# Sony_PSP_USB-C.net
KiCad netlist of a schematic drawn in EAGLE
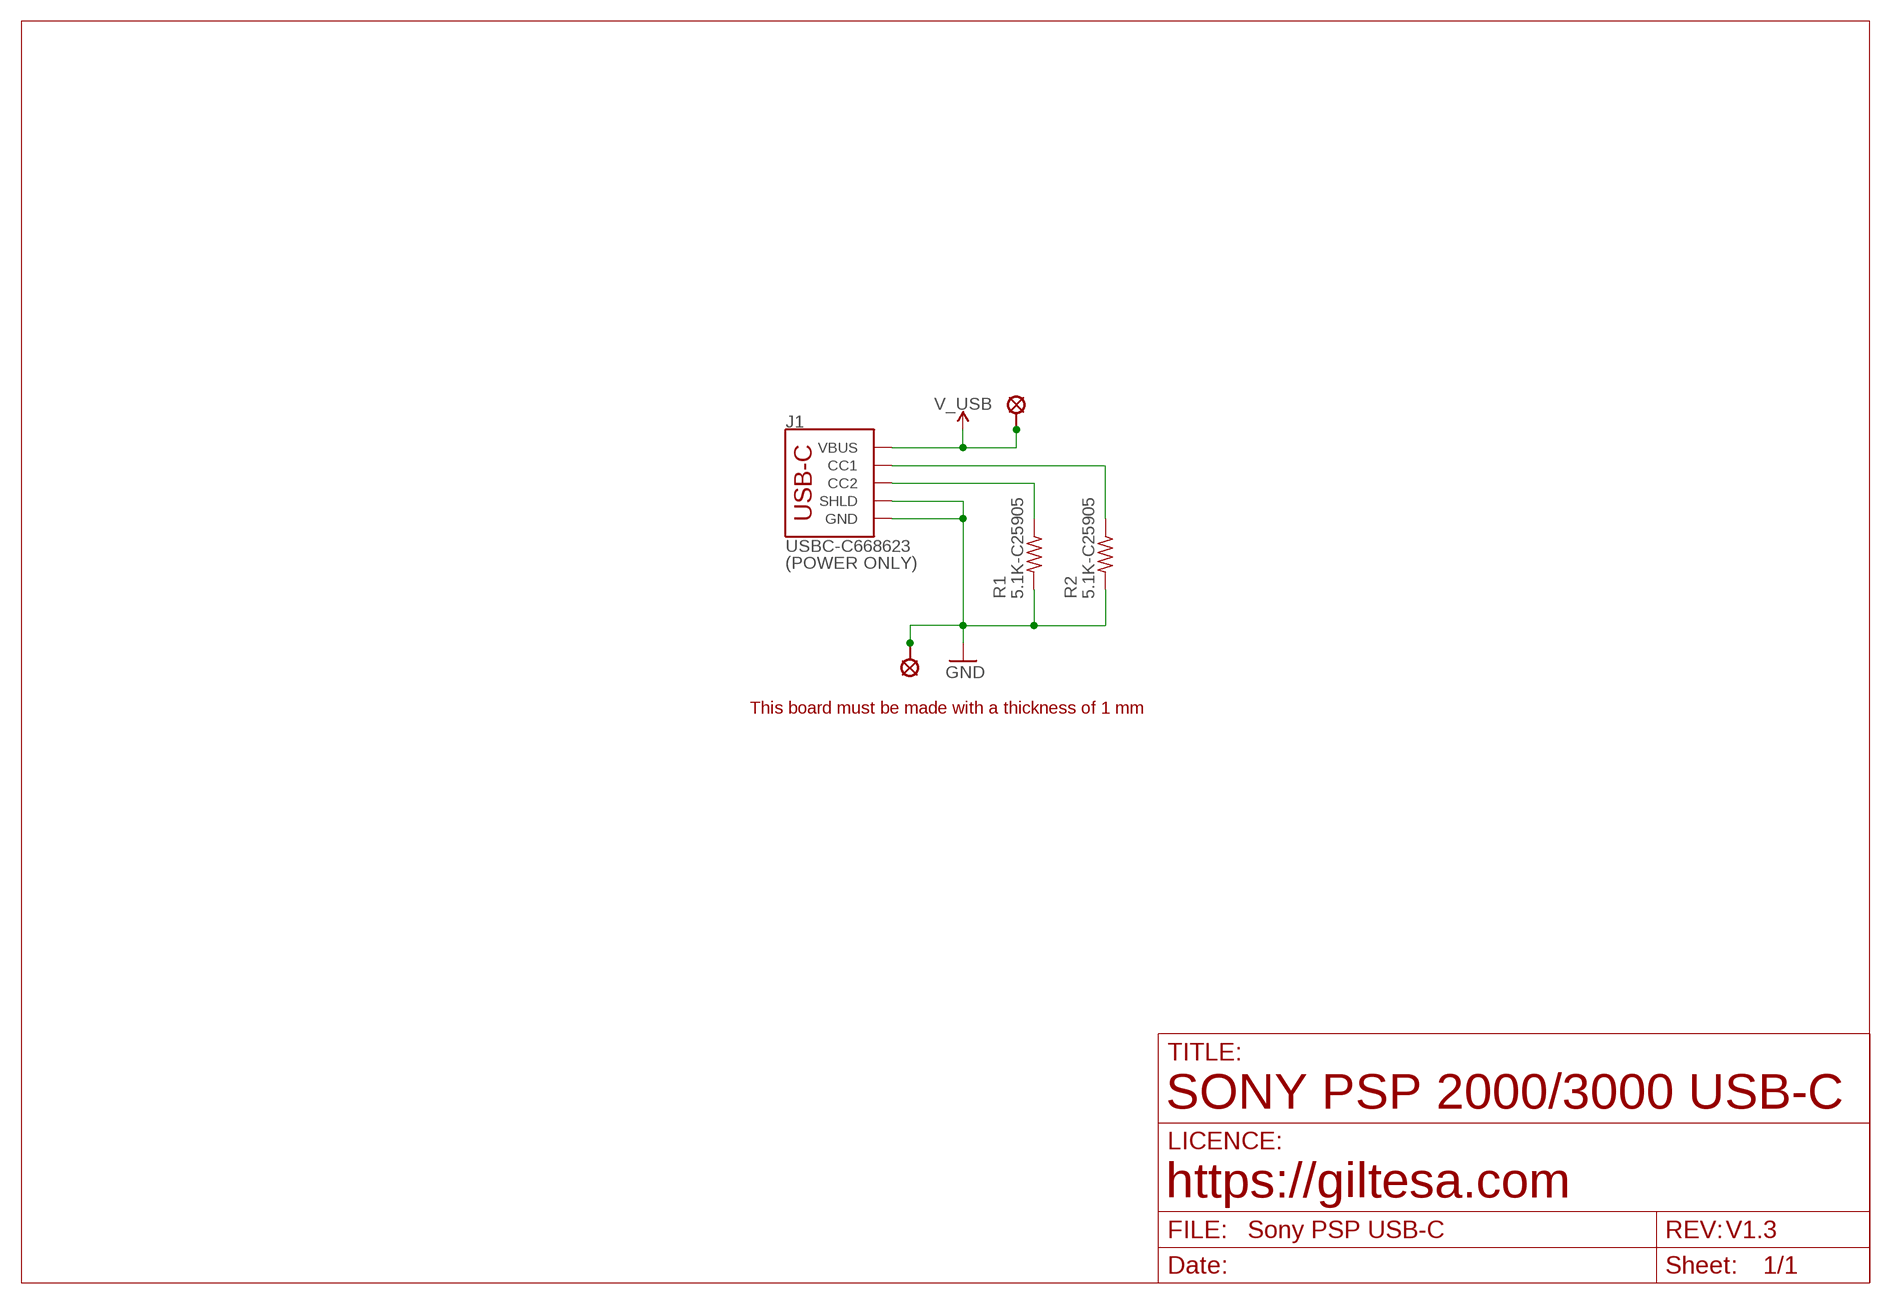
[diagram p0: schematic, sheet 1]

(export (version "E")
  (design (tool "Eeschema 10.0.6"))
  (components
    (comp (ref "J1")
      (value "USBC-C668623")
      (footprint "eagle-import:USB-C_6P")
      (libsource (lib "eagle-import") (part "USB-C_6P_POWER"))
    )
    (comp (ref "R1")
      (value "5.1K-C25905")
      (footprint "eagle-import:R0402")
      (libsource (lib "eagle-import") (part "R0402"))
    )
    (comp (ref "R2")
      (value "5.1K-C25905")
      (footprint "eagle-import:R0402")
      (libsource (lib "eagle-import") (part "R0402"))
    )
    (comp (ref "U$1")
      (value "SOLDER_PAD_N3DS")
      (footprint "eagle-import:N3DS_TPAD")
      (libsource (lib "eagle-import") (part "SOLDER_PAD_N3DS"))
    )
    (comp (ref "U$2")
      (value "SOLDER_PAD_N3DS")
      (footprint "eagle-import:N3DS_TPAD")
      (libsource (lib "eagle-import") (part "SOLDER_PAD_N3DS"))
    )
    (comp (ref "U$3")
      (value "SOLDER_PAD_N3DS")
      (footprint "eagle-import:N3DS_TPAD")
      (libsource (lib "eagle-import") (part "SOLDER_PAD_N3DS"))
    )
    (comp (ref "U$4")
      (value "SOLDER_PAD_N3DS")
      (footprint "eagle-import:N3DS_TPAD")
      (libsource (lib "eagle-import") (part "SOLDER_PAD_N3DS"))
    )
  )
  (nets
    (net (code "1") (name "GND") (class "Default")
      (node (ref "J1") (pin "A12-GND") (pinfunction "GND_A12-GND") (pintype "bidirectional"))
      (node (ref "J1") (pin "B12-GND") (pinfunction "GND_B12-GND") (pintype "bidirectional"))
      (node (ref "J1") (pin "SHLD1") (pinfunction "SHLD_SHLD1") (pintype "bidirectional"))
      (node (ref "J1") (pin "SHLD2") (pinfunction "SHLD_SHLD2") (pintype "bidirectional"))
      (node (ref "J1") (pin "SHLD3") (pinfunction "SHLD_SHLD3") (pintype "bidirectional"))
      (node (ref "J1") (pin "SHLD4") (pinfunction "SHLD_SHLD4") (pintype "bidirectional"))
      (node (ref "R1") (pin "2") (pinfunction "2_2") (pintype "passive"))
      (node (ref "R2") (pin "2") (pinfunction "2_2") (pintype "passive"))
      (node (ref "U$1") (pin "1") (pinfunction "P$1_1") (pintype "bidirectional"))
      (node (ref "U$4") (pin "1") (pinfunction "P$1_1") (pintype "bidirectional"))
    )
    (net (code "2") (name "Net-(J1-CC1)") (class "Default")
      (node (ref "J1") (pin "A5") (pinfunction "CC1_A5") (pintype "bidirectional"))
      (node (ref "R2") (pin "1") (pinfunction "1_1") (pintype "passive"))
    )
    (net (code "3") (name "Net-(J1-CC2)") (class "Default")
      (node (ref "J1") (pin "B5") (pinfunction "CC2_B5") (pintype "bidirectional"))
      (node (ref "R1") (pin "1") (pinfunction "1_1") (pintype "passive"))
    )
    (net (code "4") (name "V_USB") (class "Default")
      (node (ref "J1") (pin "A9-VBUS") (pinfunction "VBUS_A9-VBUS") (pintype "bidirectional"))
      (node (ref "J1") (pin "B9-VBUS") (pinfunction "VBUS_B9-VBUS") (pintype "bidirectional"))
      (node (ref "U$2") (pin "1") (pinfunction "P$1_1") (pintype "bidirectional"))
      (node (ref "U$3") (pin "1") (pinfunction "P$1_1") (pintype "bidirectional"))
    )
  )
)
